# Adafruit_DotStar_Wing.net
KiCad netlist of a schematic drawn in EAGLE
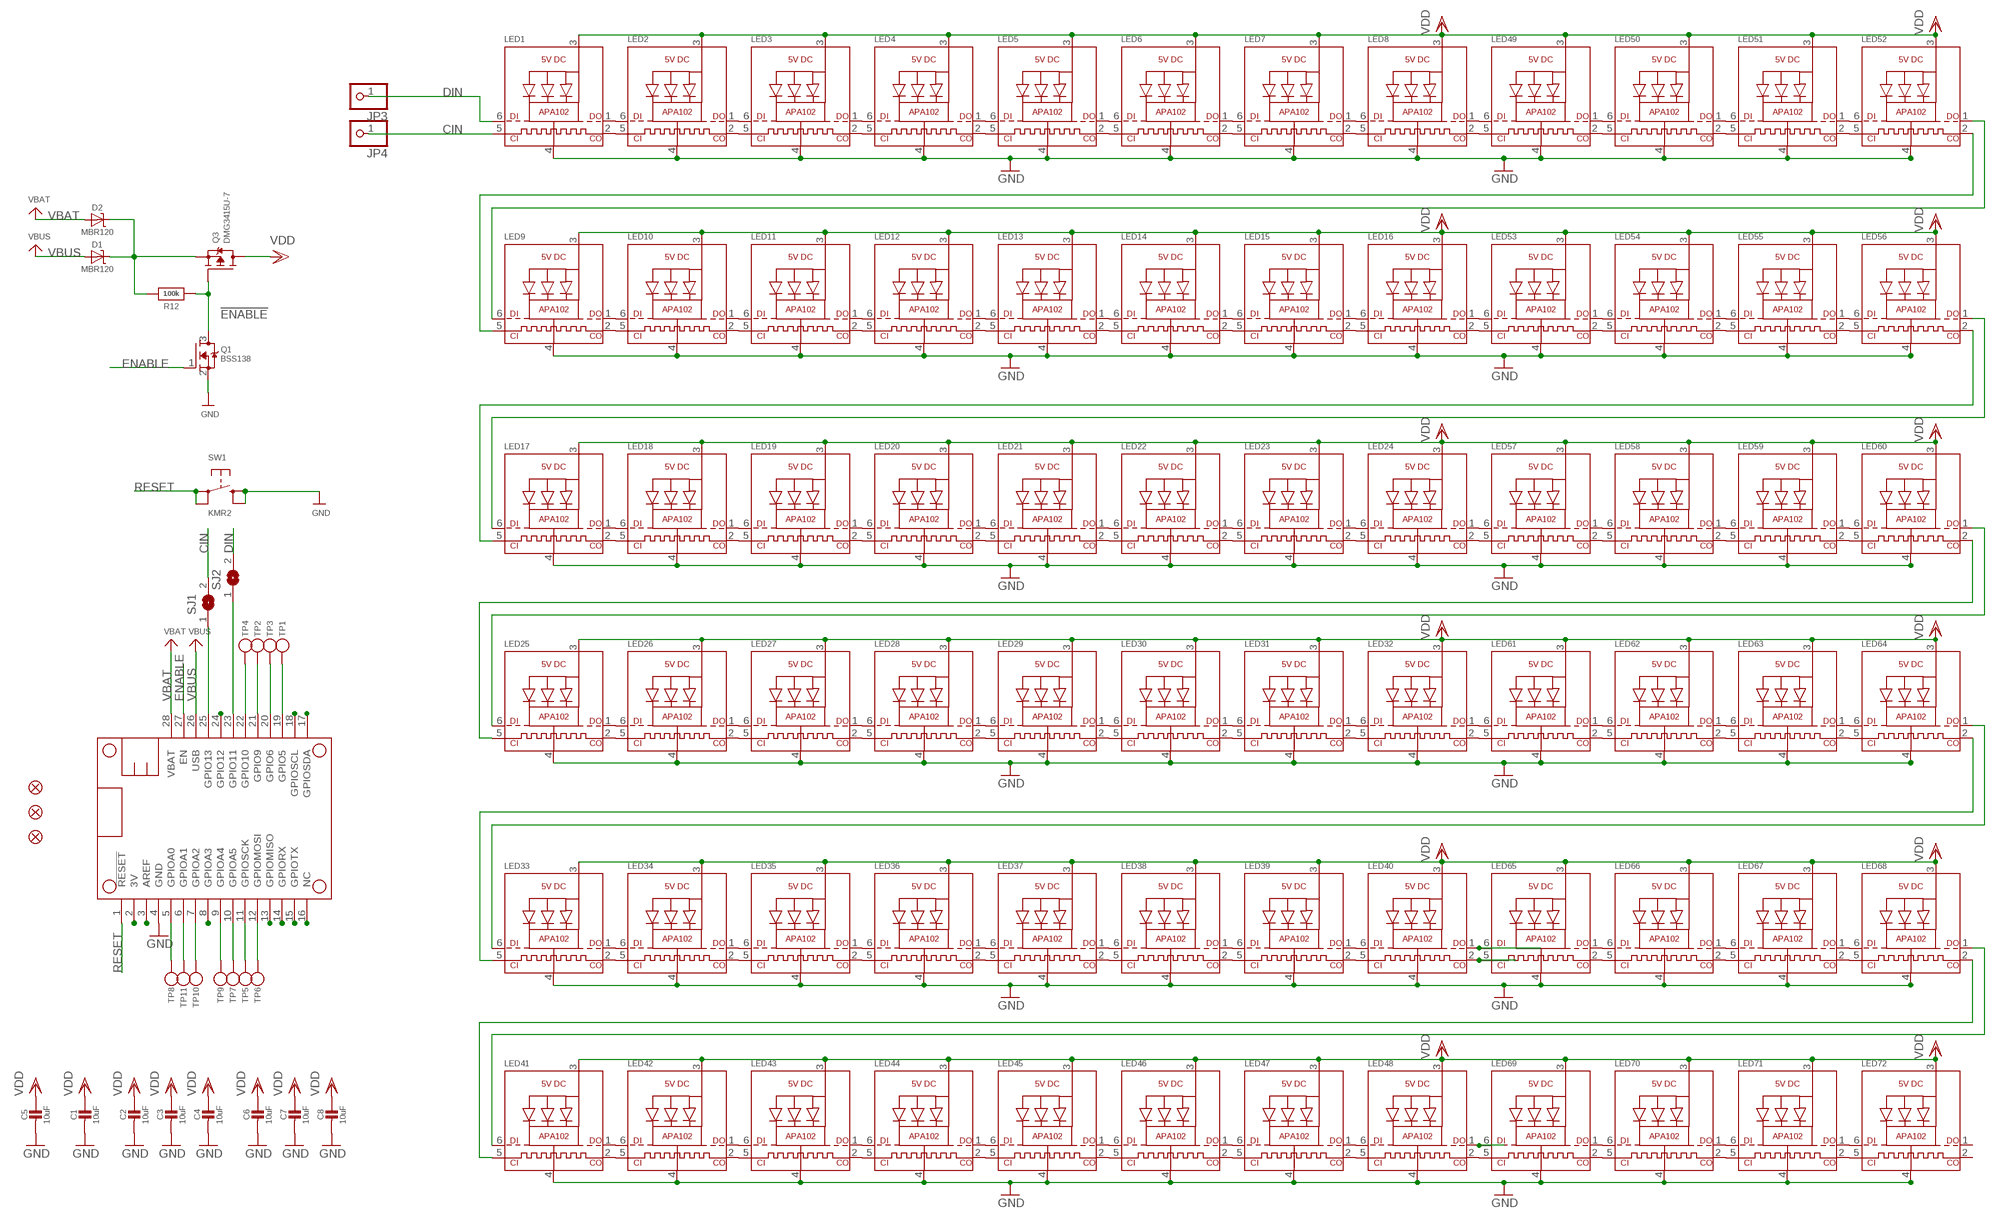
[diagram p0: schematic, sheet 1]

(export (version "E")
  (design (tool "Eeschema 10.0.6"))
  (components
    (comp (ref "C1")
      (value "10uF")
      (footprint "eagle-import:0805-NO")
      (libsource (lib "eagle-import") (part "CAP_CERAMIC0805-NOOUTLINE"))
    )
    (comp (ref "C2")
      (value "10uF")
      (footprint "eagle-import:0805-NO")
      (libsource (lib "eagle-import") (part "CAP_CERAMIC0805-NOOUTLINE"))
    )
    (comp (ref "C3")
      (value "10uF")
      (footprint "eagle-import:0805-NO")
      (libsource (lib "eagle-import") (part "CAP_CERAMIC0805-NOOUTLINE"))
    )
    (comp (ref "C4")
      (value "10uF")
      (footprint "eagle-import:0805-NO")
      (libsource (lib "eagle-import") (part "CAP_CERAMIC0805-NOOUTLINE"))
    )
    (comp (ref "C5")
      (value "10uF")
      (footprint "eagle-import:0805-NO")
      (libsource (lib "eagle-import") (part "CAP_CERAMIC0805-NOOUTLINE"))
    )
    (comp (ref "C6")
      (value "10uF")
      (footprint "eagle-import:0805-NO")
      (libsource (lib "eagle-import") (part "CAP_CERAMIC0805-NOOUTLINE"))
    )
    (comp (ref "C7")
      (value "10uF")
      (footprint "eagle-import:0805-NO")
      (libsource (lib "eagle-import") (part "CAP_CERAMIC0805-NOOUTLINE"))
    )
    (comp (ref "C8")
      (value "10uF")
      (footprint "eagle-import:0805-NO")
      (libsource (lib "eagle-import") (part "CAP_CERAMIC0805-NOOUTLINE"))
    )
    (comp (ref "D1")
      (value "MBR120")
      (footprint "eagle-import:SOD-123")
      (libsource (lib "eagle-import") (part "DIODE-SCHOTTKYSOD-123"))
    )
    (comp (ref "D2")
      (value "MBR120")
      (footprint "eagle-import:SOD-123")
      (libsource (lib "eagle-import") (part "DIODE-SCHOTTKYSOD-123"))
    )
    (comp (ref "FID1")
      (value "FIDUCIAL_1MM")
      (footprint "eagle-import:FIDUCIAL_1MM")
      (libsource (lib "eagle-import") (part "FIDUCIAL_1MM"))
    )
    (comp (ref "FID2")
      (value "FIDUCIAL_1MM")
      (footprint "eagle-import:FIDUCIAL_1MM")
      (libsource (lib "eagle-import") (part "FIDUCIAL_1MM"))
    )
    (comp (ref "FID3")
      (value "FIDUCIAL_1MM")
      (footprint "eagle-import:FIDUCIAL_1MM")
      (libsource (lib "eagle-import") (part "FIDUCIAL_1MM"))
    )
    (comp (ref "JP3")
      (value "HEADER-1X1ROUND")
      (footprint "eagle-import:1X01_ROUND")
      (libsource (lib "eagle-import") (part "HEADER-1X1ROUND"))
    )
    (comp (ref "JP4")
      (value "HEADER-1X1ROUND")
      (footprint "eagle-import:1X01_ROUND")
      (libsource (lib "eagle-import") (part "HEADER-1X1ROUND"))
    )
    (comp (ref "LED1")
      (value "APA1022020")
      (footprint "eagle-import:APA102_2020")
      (libsource (lib "eagle-import") (part "APA1022020"))
    )
    (comp (ref "LED2")
      (value "APA1022020")
      (footprint "eagle-import:APA102_2020")
      (libsource (lib "eagle-import") (part "APA1022020"))
    )
    (comp (ref "LED3")
      (value "APA1022020")
      (footprint "eagle-import:APA102_2020")
      (libsource (lib "eagle-import") (part "APA1022020"))
    )
    (comp (ref "LED4")
      (value "APA1022020")
      (footprint "eagle-import:APA102_2020")
      (libsource (lib "eagle-import") (part "APA1022020"))
    )
    (comp (ref "LED5")
      (value "APA1022020")
      (footprint "eagle-import:APA102_2020")
      (libsource (lib "eagle-import") (part "APA1022020"))
    )
    (comp (ref "LED6")
      (value "APA1022020")
      (footprint "eagle-import:APA102_2020")
      (libsource (lib "eagle-import") (part "APA1022020"))
    )
    (comp (ref "LED7")
      (value "APA1022020")
      (footprint "eagle-import:APA102_2020")
      (libsource (lib "eagle-import") (part "APA1022020"))
    )
    (comp (ref "LED8")
      (value "APA1022020")
      (footprint "eagle-import:APA102_2020")
      (libsource (lib "eagle-import") (part "APA1022020"))
    )
    (comp (ref "LED9")
      (value "APA1022020")
      (footprint "eagle-import:APA102_2020")
      (libsource (lib "eagle-import") (part "APA1022020"))
    )
    (comp (ref "LED10")
      (value "APA1022020")
      (footprint "eagle-import:APA102_2020")
      (libsource (lib "eagle-import") (part "APA1022020"))
    )
    (comp (ref "LED11")
      (value "APA1022020")
      (footprint "eagle-import:APA102_2020")
      (libsource (lib "eagle-import") (part "APA1022020"))
    )
    (comp (ref "LED12")
      (value "APA1022020")
      (footprint "eagle-import:APA102_2020")
      (libsource (lib "eagle-import") (part "APA1022020"))
    )
    (comp (ref "LED13")
      (value "APA1022020")
      (footprint "eagle-import:APA102_2020")
      (libsource (lib "eagle-import") (part "APA1022020"))
    )
    (comp (ref "LED14")
      (value "APA1022020")
      (footprint "eagle-import:APA102_2020")
      (libsource (lib "eagle-import") (part "APA1022020"))
    )
    (comp (ref "LED15")
      (value "APA1022020")
      (footprint "eagle-import:APA102_2020")
      (libsource (lib "eagle-import") (part "APA1022020"))
    )
    (comp (ref "LED16")
      (value "APA1022020")
      (footprint "eagle-import:APA102_2020")
      (libsource (lib "eagle-import") (part "APA1022020"))
    )
    (comp (ref "LED17")
      (value "APA1022020")
      (footprint "eagle-import:APA102_2020")
      (libsource (lib "eagle-import") (part "APA1022020"))
    )
    (comp (ref "LED18")
      (value "APA1022020")
      (footprint "eagle-import:APA102_2020")
      (libsource (lib "eagle-import") (part "APA1022020"))
    )
    (comp (ref "LED19")
      (value "APA1022020")
      (footprint "eagle-import:APA102_2020")
      (libsource (lib "eagle-import") (part "APA1022020"))
    )
    (comp (ref "LED20")
      (value "APA1022020")
      (footprint "eagle-import:APA102_2020")
      (libsource (lib "eagle-import") (part "APA1022020"))
    )
    (comp (ref "LED21")
      (value "APA1022020")
      (footprint "eagle-import:APA102_2020")
      (libsource (lib "eagle-import") (part "APA1022020"))
    )
    (comp (ref "LED22")
      (value "APA1022020")
      (footprint "eagle-import:APA102_2020")
      (libsource (lib "eagle-import") (part "APA1022020"))
    )
    (comp (ref "LED23")
      (value "APA1022020")
      (footprint "eagle-import:APA102_2020")
      (libsource (lib "eagle-import") (part "APA1022020"))
    )
    (comp (ref "LED24")
      (value "APA1022020")
      (footprint "eagle-import:APA102_2020")
      (libsource (lib "eagle-import") (part "APA1022020"))
    )
    (comp (ref "LED25")
      (value "APA1022020")
      (footprint "eagle-import:APA102_2020")
      (libsource (lib "eagle-import") (part "APA1022020"))
    )
    (comp (ref "LED26")
      (value "APA1022020")
      (footprint "eagle-import:APA102_2020")
      (libsource (lib "eagle-import") (part "APA1022020"))
    )
    (comp (ref "LED27")
      (value "APA1022020")
      (footprint "eagle-import:APA102_2020")
      (libsource (lib "eagle-import") (part "APA1022020"))
    )
    (comp (ref "LED28")
      (value "APA1022020")
      (footprint "eagle-import:APA102_2020")
      (libsource (lib "eagle-import") (part "APA1022020"))
    )
    (comp (ref "LED29")
      (value "APA1022020")
      (footprint "eagle-import:APA102_2020")
      (libsource (lib "eagle-import") (part "APA1022020"))
    )
    (comp (ref "LED30")
      (value "APA1022020")
      (footprint "eagle-import:APA102_2020")
      (libsource (lib "eagle-import") (part "APA1022020"))
    )
    (comp (ref "LED31")
      (value "APA1022020")
      (footprint "eagle-import:APA102_2020")
      (libsource (lib "eagle-import") (part "APA1022020"))
    )
    (comp (ref "LED32")
      (value "APA1022020")
      (footprint "eagle-import:APA102_2020")
      (libsource (lib "eagle-import") (part "APA1022020"))
    )
    (comp (ref "LED33")
      (value "APA1022020")
      (footprint "eagle-import:APA102_2020")
      (libsource (lib "eagle-import") (part "APA1022020"))
    )
    (comp (ref "LED34")
      (value "APA1022020")
      (footprint "eagle-import:APA102_2020")
      (libsource (lib "eagle-import") (part "APA1022020"))
    )
    (comp (ref "LED35")
      (value "APA1022020")
      (footprint "eagle-import:APA102_2020")
      (libsource (lib "eagle-import") (part "APA1022020"))
    )
    (comp (ref "LED36")
      (value "APA1022020")
      (footprint "eagle-import:APA102_2020")
      (libsource (lib "eagle-import") (part "APA1022020"))
    )
    (comp (ref "LED37")
      (value "APA1022020")
      (footprint "eagle-import:APA102_2020")
      (libsource (lib "eagle-import") (part "APA1022020"))
    )
    (comp (ref "LED38")
      (value "APA1022020")
      (footprint "eagle-import:APA102_2020")
      (libsource (lib "eagle-import") (part "APA1022020"))
    )
    (comp (ref "LED39")
      (value "APA1022020")
      (footprint "eagle-import:APA102_2020")
      (libsource (lib "eagle-import") (part "APA1022020"))
    )
    (comp (ref "LED40")
      (value "APA1022020")
      (footprint "eagle-import:APA102_2020")
      (libsource (lib "eagle-import") (part "APA1022020"))
    )
    (comp (ref "LED41")
      (value "APA1022020")
      (footprint "eagle-import:APA102_2020")
      (libsource (lib "eagle-import") (part "APA1022020"))
    )
    (comp (ref "LED42")
      (value "APA1022020")
      (footprint "eagle-import:APA102_2020")
      (libsource (lib "eagle-import") (part "APA1022020"))
    )
    (comp (ref "LED43")
      (value "APA1022020")
      (footprint "eagle-import:APA102_2020")
      (libsource (lib "eagle-import") (part "APA1022020"))
    )
    (comp (ref "LED44")
      (value "APA1022020")
      (footprint "eagle-import:APA102_2020")
      (libsource (lib "eagle-import") (part "APA1022020"))
    )
    (comp (ref "LED45")
      (value "APA1022020")
      (footprint "eagle-import:APA102_2020")
      (libsource (lib "eagle-import") (part "APA1022020"))
    )
    (comp (ref "LED46")
      (value "APA1022020")
      (footprint "eagle-import:APA102_2020")
      (libsource (lib "eagle-import") (part "APA1022020"))
    )
    (comp (ref "LED47")
      (value "APA1022020")
      (footprint "eagle-import:APA102_2020")
      (libsource (lib "eagle-import") (part "APA1022020"))
    )
    (comp (ref "LED48")
      (value "APA1022020")
      (footprint "eagle-import:APA102_2020")
      (libsource (lib "eagle-import") (part "APA1022020"))
    )
    (comp (ref "LED49")
      (value "APA1022020")
      (footprint "eagle-import:APA102_2020")
      (libsource (lib "eagle-import") (part "APA1022020"))
    )
    (comp (ref "LED50")
      (value "APA1022020")
      (footprint "eagle-import:APA102_2020")
      (libsource (lib "eagle-import") (part "APA1022020"))
    )
    (comp (ref "LED51")
      (value "APA1022020")
      (footprint "eagle-import:APA102_2020")
      (libsource (lib "eagle-import") (part "APA1022020"))
    )
    (comp (ref "LED52")
      (value "APA1022020")
      (footprint "eagle-import:APA102_2020")
      (libsource (lib "eagle-import") (part "APA1022020"))
    )
    (comp (ref "LED53")
      (value "APA1022020")
      (footprint "eagle-import:APA102_2020")
      (libsource (lib "eagle-import") (part "APA1022020"))
    )
    (comp (ref "LED54")
      (value "APA1022020")
      (footprint "eagle-import:APA102_2020")
      (libsource (lib "eagle-import") (part "APA1022020"))
    )
    (comp (ref "LED55")
      (value "APA1022020")
      (footprint "eagle-import:APA102_2020")
      (libsource (lib "eagle-import") (part "APA1022020"))
    )
    (comp (ref "LED56")
      (value "APA1022020")
      (footprint "eagle-import:APA102_2020")
      (libsource (lib "eagle-import") (part "APA1022020"))
    )
    (comp (ref "LED57")
      (value "APA1022020")
      (footprint "eagle-import:APA102_2020")
      (libsource (lib "eagle-import") (part "APA1022020"))
    )
    (comp (ref "LED58")
      (value "APA1022020")
      (footprint "eagle-import:APA102_2020")
      (libsource (lib "eagle-import") (part "APA1022020"))
    )
    (comp (ref "LED59")
      (value "APA1022020")
      (footprint "eagle-import:APA102_2020")
      (libsource (lib "eagle-import") (part "APA1022020"))
    )
    (comp (ref "LED60")
      (value "APA1022020")
      (footprint "eagle-import:APA102_2020")
      (libsource (lib "eagle-import") (part "APA1022020"))
    )
    (comp (ref "LED61")
      (value "APA1022020")
      (footprint "eagle-import:APA102_2020")
      (libsource (lib "eagle-import") (part "APA1022020"))
    )
    (comp (ref "LED62")
      (value "APA1022020")
      (footprint "eagle-import:APA102_2020")
      (libsource (lib "eagle-import") (part "APA1022020"))
    )
    (comp (ref "LED63")
      (value "APA1022020")
      (footprint "eagle-import:APA102_2020")
      (libsource (lib "eagle-import") (part "APA1022020"))
    )
    (comp (ref "LED64")
      (value "APA1022020")
      (footprint "eagle-import:APA102_2020")
      (libsource (lib "eagle-import") (part "APA1022020"))
    )
    (comp (ref "LED65")
      (value "APA1022020")
      (footprint "eagle-import:APA102_2020")
      (libsource (lib "eagle-import") (part "APA1022020"))
    )
    (comp (ref "LED66")
      (value "APA1022020")
      (footprint "eagle-import:APA102_2020")
      (libsource (lib "eagle-import") (part "APA1022020"))
    )
    (comp (ref "LED67")
      (value "APA1022020")
      (footprint "eagle-import:APA102_2020")
      (libsource (lib "eagle-import") (part "APA1022020"))
    )
    (comp (ref "LED68")
      (value "APA1022020")
      (footprint "eagle-import:APA102_2020")
      (libsource (lib "eagle-import") (part "APA1022020"))
    )
    (comp (ref "LED69")
      (value "APA1022020")
      (footprint "eagle-import:APA102_2020")
      (libsource (lib "eagle-import") (part "APA1022020"))
    )
    (comp (ref "LED70")
      (value "APA1022020")
      (footprint "eagle-import:APA102_2020")
      (libsource (lib "eagle-import") (part "APA1022020"))
    )
    (comp (ref "LED71")
      (value "APA1022020")
      (footprint "eagle-import:APA102_2020")
      (libsource (lib "eagle-import") (part "APA1022020"))
    )
    (comp (ref "LED72")
      (value "APA1022020")
      (footprint "eagle-import:APA102_2020")
      (libsource (lib "eagle-import") (part "APA1022020"))
    )
    (comp (ref "MS1")
      (value "FEATHERWING")
      (footprint "eagle-import:FEATHERWING")
      (libsource (lib "eagle-import") (part "FEATHERWING"))
    )
    (comp (ref "Q1")
      (value "BSS138")
      (footprint "eagle-import:SOT23-WIDE")
      (libsource (lib "eagle-import") (part "MOSFET-NWIDE"))
    )
    (comp (ref "Q3")
      (value "DMG3415U-7")
      (footprint "eagle-import:SOT23-WIDE")
      (libsource (lib "eagle-import") (part "MOSFET-PWIDE"))
    )
    (comp (ref "R12")
      (value "100k")
      (footprint "eagle-import:0603-NO")
      (libsource (lib "eagle-import") (part "RESISTOR_0603_NOOUT"))
    )
    (comp (ref "SJ1")
      (value "SOLDERJUMPERCLOSED")
      (footprint "eagle-import:SOLDERJUMPER_CLOSEDWIRE")
      (libsource (lib "eagle-import") (part "SOLDERJUMPERCLOSED"))
    )
    (comp (ref "SJ2")
      (value "SOLDERJUMPERCLOSED")
      (footprint "eagle-import:SOLDERJUMPER_CLOSEDWIRE")
      (libsource (lib "eagle-import") (part "SOLDERJUMPERCLOSED"))
    )
    (comp (ref "SW1")
      (value "KMR2")
      (footprint "eagle-import:BTN_KMR2_4.6X2.8")
      (libsource (lib "eagle-import") (part "SWITCH_TACT_SMT4.6X2.8"))
    )
    (comp (ref "TP1")
      (value "TESTPOINT1.5X2.0MM_NOCREAM")
      (footprint "eagle-import:PAD-1.5X2.0")
      (libsource (lib "eagle-import") (part "TESTPOINT1.5X2.0MM_NOCREAM"))
    )
    (comp (ref "TP2")
      (value "TESTPOINT1.5X2.0MM_NOCREAM")
      (footprint "eagle-import:PAD-1.5X2.0")
      (libsource (lib "eagle-import") (part "TESTPOINT1.5X2.0MM_NOCREAM"))
    )
    (comp (ref "TP3")
      (value "TESTPOINT1.5X2.0MM_NOCREAM")
      (footprint "eagle-import:PAD-1.5X2.0")
      (libsource (lib "eagle-import") (part "TESTPOINT1.5X2.0MM_NOCREAM"))
    )
    (comp (ref "TP4")
      (value "TESTPOINT1.5X2.0MM_NOCREAM")
      (footprint "eagle-import:PAD-1.5X2.0")
      (libsource (lib "eagle-import") (part "TESTPOINT1.5X2.0MM_NOCREAM"))
    )
    (comp (ref "TP5")
      (value "TESTPOINT1.5X2.0MM_NOCREAM")
      (footprint "eagle-import:PAD-1.5X2.0")
      (libsource (lib "eagle-import") (part "TESTPOINT1.5X2.0MM_NOCREAM"))
    )
    (comp (ref "TP6")
      (value "TESTPOINT1.5X2.0MM_NOCREAM")
      (footprint "eagle-import:PAD-1.5X2.0")
      (libsource (lib "eagle-import") (part "TESTPOINT1.5X2.0MM_NOCREAM"))
    )
    (comp (ref "TP7")
      (value "TESTPOINT1.5X2.0MM_NOCREAM")
      (footprint "eagle-import:PAD-1.5X2.0")
      (libsource (lib "eagle-import") (part "TESTPOINT1.5X2.0MM_NOCREAM"))
    )
    (comp (ref "TP8")
      (value "TESTPOINT1.5X2.0MM_NOCREAM")
      (footprint "eagle-import:PAD-1.5X2.0")
      (libsource (lib "eagle-import") (part "TESTPOINT1.5X2.0MM_NOCREAM"))
    )
    (comp (ref "TP9")
      (value "TESTPOINT1.5X2.0MM_NOCREAM")
      (footprint "eagle-import:PAD-1.5X2.0")
      (libsource (lib "eagle-import") (part "TESTPOINT1.5X2.0MM_NOCREAM"))
    )
    (comp (ref "TP10")
      (value "TESTPOINT1.5X2.0MM_NOCREAM")
      (footprint "eagle-import:PAD-1.5X2.0")
      (libsource (lib "eagle-import") (part "TESTPOINT1.5X2.0MM_NOCREAM"))
    )
    (comp (ref "TP11")
      (value "TESTPOINT1.5X2.0MM_NOCREAM")
      (footprint "eagle-import:PAD-1.5X2.0")
      (libsource (lib "eagle-import") (part "TESTPOINT1.5X2.0MM_NOCREAM"))
    )
  )
  (nets
    (net (code "1") (name "/3V") (class "Default")
      (node (ref "MS1") (pin "2") (pinfunction "3V_2") (pintype "power_in"))
    )
    (net (code "2") (name "/CIN") (class "Default")
      (node (ref "JP4") (pin "1") (pinfunction "1_1") (pintype "passive"))
      (node (ref "LED1") (pin "5") (pinfunction "CKI_5") (pintype "input"))
      (node (ref "SJ1") (pin "2") (pinfunction "2_2") (pintype "passive"))
    )
    (net (code "3") (name "/DIN") (class "Default")
      (node (ref "JP3") (pin "1") (pinfunction "1_1") (pintype "passive"))
      (node (ref "LED1") (pin "6") (pinfunction "DI_6") (pintype "input"))
      (node (ref "SJ2") (pin "2") (pinfunction "2_2") (pintype "passive"))
    )
    (net (code "4") (name "/ENABLE") (class "Default")
      (node (ref "MS1") (pin "27") (pinfunction "EN_27") (pintype "passive"))
      (node (ref "Q1") (pin "1") (pinfunction "G_1") (pintype "bidirectional"))
    )
    (net (code "5") (name "/RESET") (class "Default")
      (node (ref "MS1") (pin "1") (pinfunction "~{RESET}_1") (pintype "input"))
      (node (ref "SW1") (pin "A") (pinfunction "P_A") (pintype "passive"))
      (node (ref "SW1") (pin "A'") (pinfunction "P1_A'") (pintype "passive"))
    )
    (net (code "6") (name "/~{ENABLE}") (class "Default")
      (node (ref "Q1") (pin "3") (pinfunction "D_3") (pintype "bidirectional"))
      (node (ref "Q3") (pin "1") (pinfunction "G_1") (pintype "passive"))
      (node (ref "R12") (pin "1") (pinfunction "1_1") (pintype "passive"))
    )
    (net (code "7") (name "GND") (class "Default")
      (node (ref "C1") (pin "2") (pinfunction "2_2") (pintype "passive"))
      (node (ref "C2") (pin "2") (pinfunction "2_2") (pintype "passive"))
      (node (ref "C3") (pin "2") (pinfunction "2_2") (pintype "passive"))
      (node (ref "C4") (pin "2") (pinfunction "2_2") (pintype "passive"))
      (node (ref "C5") (pin "2") (pinfunction "2_2") (pintype "passive"))
      (node (ref "C6") (pin "2") (pinfunction "2_2") (pintype "passive"))
      (node (ref "C7") (pin "2") (pinfunction "2_2") (pintype "passive"))
      (node (ref "C8") (pin "2") (pinfunction "2_2") (pintype "passive"))
      (node (ref "LED1") (pin "4") (pinfunction "GND_4") (pintype "power_in"))
      (node (ref "LED10") (pin "4") (pinfunction "GND_4") (pintype "power_in"))
      (node (ref "LED11") (pin "4") (pinfunction "GND_4") (pintype "power_in"))
      (node (ref "LED12") (pin "4") (pinfunction "GND_4") (pintype "power_in"))
      (node (ref "LED13") (pin "4") (pinfunction "GND_4") (pintype "power_in"))
      (node (ref "LED14") (pin "4") (pinfunction "GND_4") (pintype "power_in"))
      (node (ref "LED15") (pin "4") (pinfunction "GND_4") (pintype "power_in"))
      (node (ref "LED16") (pin "4") (pinfunction "GND_4") (pintype "power_in"))
      (node (ref "LED17") (pin "4") (pinfunction "GND_4") (pintype "power_in"))
      (node (ref "LED18") (pin "4") (pinfunction "GND_4") (pintype "power_in"))
      (node (ref "LED19") (pin "4") (pinfunction "GND_4") (pintype "power_in"))
      (node (ref "LED2") (pin "4") (pinfunction "GND_4") (pintype "power_in"))
      (node (ref "LED20") (pin "4") (pinfunction "GND_4") (pintype "power_in"))
      (node (ref "LED21") (pin "4") (pinfunction "GND_4") (pintype "power_in"))
      (node (ref "LED22") (pin "4") (pinfunction "GND_4") (pintype "power_in"))
      (node (ref "LED23") (pin "4") (pinfunction "GND_4") (pintype "power_in"))
      (node (ref "LED24") (pin "4") (pinfunction "GND_4") (pintype "power_in"))
      (node (ref "LED25") (pin "4") (pinfunction "GND_4") (pintype "power_in"))
      (node (ref "LED26") (pin "4") (pinfunction "GND_4") (pintype "power_in"))
      (node (ref "LED27") (pin "4") (pinfunction "GND_4") (pintype "power_in"))
      (node (ref "LED28") (pin "4") (pinfunction "GND_4") (pintype "power_in"))
      (node (ref "LED29") (pin "4") (pinfunction "GND_4") (pintype "power_in"))
      (node (ref "LED3") (pin "4") (pinfunction "GND_4") (pintype "power_in"))
      (node (ref "LED30") (pin "4") (pinfunction "GND_4") (pintype "power_in"))
      (node (ref "LED31") (pin "4") (pinfunction "GND_4") (pintype "power_in"))
      (node (ref "LED32") (pin "4") (pinfunction "GND_4") (pintype "power_in"))
      (node (ref "LED33") (pin "4") (pinfunction "GND_4") (pintype "power_in"))
      (node (ref "LED34") (pin "4") (pinfunction "GND_4") (pintype "power_in"))
      (node (ref "LED35") (pin "4") (pinfunction "GND_4") (pintype "power_in"))
      (node (ref "LED36") (pin "4") (pinfunction "GND_4") (pintype "power_in"))
      (node (ref "LED37") (pin "4") (pinfunction "GND_4") (pintype "power_in"))
      (node (ref "LED38") (pin "4") (pinfunction "GND_4") (pintype "power_in"))
      (node (ref "LED39") (pin "4") (pinfunction "GND_4") (pintype "power_in"))
      (node (ref "LED4") (pin "4") (pinfunction "GND_4") (pintype "power_in"))
      (node (ref "LED40") (pin "4") (pinfunction "GND_4") (pintype "power_in"))
      (node (ref "LED41") (pin "4") (pinfunction "GND_4") (pintype "power_in"))
      (node (ref "LED42") (pin "4") (pinfunction "GND_4") (pintype "power_in"))
      (node (ref "LED43") (pin "4") (pinfunction "GND_4") (pintype "power_in"))
      (node (ref "LED44") (pin "4") (pinfunction "GND_4") (pintype "power_in"))
      (node (ref "LED45") (pin "4") (pinfunction "GND_4") (pintype "power_in"))
      (node (ref "LED46") (pin "4") (pinfunction "GND_4") (pintype "power_in"))
      (node (ref "LED47") (pin "4") (pinfunction "GND_4") (pintype "power_in"))
      (node (ref "LED48") (pin "4") (pinfunction "GND_4") (pintype "power_in"))
      (node (ref "LED49") (pin "4") (pinfunction "GND_4") (pintype "power_in"))
      (node (ref "LED5") (pin "4") (pinfunction "GND_4") (pintype "power_in"))
      (node (ref "LED50") (pin "4") (pinfunction "GND_4") (pintype "power_in"))
      (node (ref "LED51") (pin "4") (pinfunction "GND_4") (pintype "power_in"))
      (node (ref "LED52") (pin "4") (pinfunction "GND_4") (pintype "power_in"))
      (node (ref "LED53") (pin "4") (pinfunction "GND_4") (pintype "power_in"))
      (node (ref "LED54") (pin "4") (pinfunction "GND_4") (pintype "power_in"))
      (node (ref "LED55") (pin "4") (pinfunction "GND_4") (pintype "power_in"))
      (node (ref "LED56") (pin "4") (pinfunction "GND_4") (pintype "power_in"))
      (node (ref "LED57") (pin "4") (pinfunction "GND_4") (pintype "power_in"))
      (node (ref "LED58") (pin "4") (pinfunction "GND_4") (pintype "power_in"))
      (node (ref "LED59") (pin "4") (pinfunction "GND_4") (pintype "power_in"))
      (node (ref "LED6") (pin "4") (pinfunction "GND_4") (pintype "power_in"))
      (node (ref "LED60") (pin "4") (pinfunction "GND_4") (pintype "power_in"))
      (node (ref "LED61") (pin "4") (pinfunction "GND_4") (pintype "power_in"))
      (node (ref "LED62") (pin "4") (pinfunction "GND_4") (pintype "power_in"))
      (node (ref "LED63") (pin "4") (pinfunction "GND_4") (pintype "power_in"))
      (node (ref "LED64") (pin "4") (pinfunction "GND_4") (pintype "power_in"))
      (node (ref "LED65") (pin "4") (pinfunction "GND_4") (pintype "power_in"))
      (node (ref "LED66") (pin "4") (pinfunction "GND_4") (pintype "power_in"))
      (node (ref "LED67") (pin "4") (pinfunction "GND_4") (pintype "power_in"))
      (node (ref "LED68") (pin "4") (pinfunction "GND_4") (pintype "power_in"))
      (node (ref "LED69") (pin "4") (pinfunction "GND_4") (pintype "power_in"))
      (node (ref "LED7") (pin "4") (pinfunction "GND_4") (pintype "power_in"))
      (node (ref "LED70") (pin "4") (pinfunction "GND_4") (pintype "power_in"))
      (node (ref "LED71") (pin "4") (pinfunction "GND_4") (pintype "power_in"))
      (node (ref "LED72") (pin "4") (pinfunction "GND_4") (pintype "power_in"))
      (node (ref "LED8") (pin "4") (pinfunction "GND_4") (pintype "power_in"))
      (node (ref "LED9") (pin "4") (pinfunction "GND_4") (pintype "power_in"))
      (node (ref "MS1") (pin "4") (pinfunction "GND_4") (pintype "power_in"))
      (node (ref "Q1") (pin "2") (pinfunction "S_2") (pintype "bidirectional"))
      (node (ref "SW1") (pin "B") (pinfunction "S_B") (pintype "passive"))
      (node (ref "SW1") (pin "B'") (pinfunction "S1_B'") (pintype "passive"))
    )
    (net (code "8") (name "Net-(LED1-CKO)") (class "Default")
      (node (ref "LED1") (pin "2") (pinfunction "CKO_2") (pintype "output"))
      (node (ref "LED2") (pin "5") (pinfunction "CKI_5") (pintype "input"))
    )
    (net (code "9") (name "Net-(LED1-DO)") (class "Default")
      (node (ref "LED1") (pin "1") (pinfunction "DO_1") (pintype "output"))
      (node (ref "LED2") (pin "6") (pinfunction "DI_6") (pintype "input"))
    )
    (net (code "10") (name "Net-(LED2-CKO)") (class "Default")
      (node (ref "LED2") (pin "2") (pinfunction "CKO_2") (pintype "output"))
      (node (ref "LED3") (pin "5") (pinfunction "CKI_5") (pintype "input"))
    )
    (net (code "11") (name "Net-(LED2-DO)") (class "Default")
      (node (ref "LED2") (pin "1") (pinfunction "DO_1") (pintype "output"))
      (node (ref "LED3") (pin "6") (pinfunction "DI_6") (pintype "input"))
    )
    (net (code "12") (name "Net-(LED3-CKO)") (class "Default")
      (node (ref "LED3") (pin "2") (pinfunction "CKO_2") (pintype "output"))
      (node (ref "LED4") (pin "5") (pinfunction "CKI_5") (pintype "input"))
    )
    (net (code "13") (name "Net-(LED3-DO)") (class "Default")
      (node (ref "LED3") (pin "1") (pinfunction "DO_1") (pintype "output"))
      (node (ref "LED4") (pin "6") (pinfunction "DI_6") (pintype "input"))
    )
    (net (code "14") (name "Net-(LED4-CKO)") (class "Default")
      (node (ref "LED4") (pin "2") (pinfunction "CKO_2") (pintype "output"))
      (node (ref "LED5") (pin "5") (pinfunction "CKI_5") (pintype "input"))
    )
    (net (code "15") (name "Net-(LED4-DO)") (class "Default")
      (node (ref "LED4") (pin "1") (pinfunction "DO_1") (pintype "output"))
      (node (ref "LED5") (pin "6") (pinfunction "DI_6") (pintype "input"))
    )
    (net (code "16") (name "Net-(LED5-CKO)") (class "Default")
      (node (ref "LED5") (pin "2") (pinfunction "CKO_2") (pintype "output"))
      (node (ref "LED6") (pin "5") (pinfunction "CKI_5") (pintype "input"))
    )
    (net (code "17") (name "Net-(LED5-DO)") (class "Default")
      (node (ref "LED5") (pin "1") (pinfunction "DO_1") (pintype "output"))
      (node (ref "LED6") (pin "6") (pinfunction "DI_6") (pintype "input"))
    )
    (net (code "18") (name "Net-(LED6-CKO)") (class "Default")
      (node (ref "LED6") (pin "2") (pinfunction "CKO_2") (pintype "output"))
      (node (ref "LED7") (pin "5") (pinfunction "CKI_5") (pintype "input"))
    )
    (net (code "19") (name "Net-(LED6-DO)") (class "Default")
      (node (ref "LED6") (pin "1") (pinfunction "DO_1") (pintype "output"))
      (node (ref "LED7") (pin "6") (pinfunction "DI_6") (pintype "input"))
    )
    (net (code "20") (name "Net-(LED7-CKO)") (class "Default")
      (node (ref "LED7") (pin "2") (pinfunction "CKO_2") (pintype "output"))
      (node (ref "LED8") (pin "5") (pinfunction "CKI_5") (pintype "input"))
    )
    (net (code "21") (name "Net-(LED7-DO)") (class "Default")
      (node (ref "LED7") (pin "1") (pinfunction "DO_1") (pintype "output"))
      (node (ref "LED8") (pin "6") (pinfunction "DI_6") (pintype "input"))
    )
    (net (code "22") (name "Net-(LED10-CKI)") (class "Default")
      (node (ref "LED10") (pin "5") (pinfunction "CKI_5") (pintype "input"))
      (node (ref "LED9") (pin "2") (pinfunction "CKO_2") (pintype "output"))
    )
    (net (code "23") (name "Net-(LED10-CKO)") (class "Default")
      (node (ref "LED10") (pin "2") (pinfunction "CKO_2") (pintype "output"))
      (node (ref "LED11") (pin "5") (pinfunction "CKI_5") (pintype "input"))
    )
    (net (code "24") (name "Net-(LED10-DI)") (class "Default")
      (node (ref "LED10") (pin "6") (pinfunction "DI_6") (pintype "input"))
      (node (ref "LED9") (pin "1") (pinfunction "DO_1") (pintype "output"))
    )
    (net (code "25") (name "Net-(LED10-DO)") (class "Default")
      (node (ref "LED10") (pin "1") (pinfunction "DO_1") (pintype "output"))
      (node (ref "LED11") (pin "6") (pinfunction "DI_6") (pintype "input"))
    )
    (net (code "26") (name "Net-(LED11-CKO)") (class "Default")
      (node (ref "LED11") (pin "2") (pinfunction "CKO_2") (pintype "output"))
      (node (ref "LED12") (pin "5") (pinfunction "CKI_5") (pintype "input"))
    )
    (net (code "27") (name "Net-(LED11-DO)") (class "Default")
      (node (ref "LED11") (pin "1") (pinfunction "DO_1") (pintype "output"))
      (node (ref "LED12") (pin "6") (pinfunction "DI_6") (pintype "input"))
    )
    (net (code "28") (name "Net-(LED12-CKO)") (class "Default")
      (node (ref "LED12") (pin "2") (pinfunction "CKO_2") (pintype "output"))
      (node (ref "LED13") (pin "5") (pinfunction "CKI_5") (pintype "input"))
    )
    (net (code "29") (name "Net-(LED12-DO)") (class "Default")
      (node (ref "LED12") (pin "1") (pinfunction "DO_1") (pintype "output"))
      (node (ref "LED13") (pin "6") (pinfunction "DI_6") (pintype "input"))
    )
    (net (code "30") (name "Net-(LED13-CKO)") (class "Default")
      (node (ref "LED13") (pin "2") (pinfunction "CKO_2") (pintype "output"))
      (node (ref "LED14") (pin "5") (pinfunction "CKI_5") (pintype "input"))
    )
    (net (code "31") (name "Net-(LED13-DO)") (class "Default")
      (node (ref "LED13") (pin "1") (pinfunction "DO_1") (pintype "output"))
      (node (ref "LED14") (pin "6") (pinfunction "DI_6") (pintype "input"))
    )
    (net (code "32") (name "Net-(LED14-CKO)") (class "Default")
      (node (ref "LED14") (pin "2") (pinfunction "CKO_2") (pintype "output"))
      (node (ref "LED15") (pin "5") (pinfunction "CKI_5") (pintype "input"))
    )
    (net (code "33") (name "Net-(LED14-DO)") (class "Default")
      (node (ref "LED14") (pin "1") (pinfunction "DO_1") (pintype "output"))
      (node (ref "LED15") (pin "6") (pinfunction "DI_6") (pintype "input"))
    )
    (net (code "34") (name "Net-(LED15-CKO)") (class "Default")
      (node (ref "LED15") (pin "2") (pinfunction "CKO_2") (pintype "output"))
      (node (ref "LED16") (pin "5") (pinfunction "CKI_5") (pintype "input"))
    )
    (net (code "35") (name "Net-(LED15-DO)") (class "Default")
      (node (ref "LED15") (pin "1") (pinfunction "DO_1") (pintype "output"))
      (node (ref "LED16") (pin "6") (pinfunction "DI_6") (pintype "input"))
    )
    (net (code "36") (name "Net-(LED16-CKO)") (class "Default")
      (node (ref "LED16") (pin "2") (pinfunction "CKO_2") (pintype "output"))
      (node (ref "LED53") (pin "5") (pinfunction "CKI_5") (pintype "input"))
    )
    (net (code "37") (name "Net-(LED16-DO)") (class "Default")
      (node (ref "LED16") (pin "1") (pinfunction "DO_1") (pintype "output"))
      (node (ref "LED53") (pin "6") (pinfunction "DI_6") (pintype "input"))
    )
    (net (code "38") (name "Net-(LED17-CKI)") (class "Default")
      (node (ref "LED17") (pin "5") (pinfunction "CKI_5") (pintype "input"))
      (node (ref "LED56") (pin "2") (pinfunction "CKO_2") (pintype "output"))
    )
    (net (code "39") (name "Net-(LED17-CKO)") (class "Default")
      (node (ref "LED17") (pin "2") (pinfunction "CKO_2") (pintype "output"))
      (node (ref "LED18") (pin "5") (pinfunction "CKI_5") (pintype "input"))
    )
    (net (code "40") (name "Net-(LED17-DI)") (class "Default")
      (node (ref "LED17") (pin "6") (pinfunction "DI_6") (pintype "input"))
      (node (ref "LED56") (pin "1") (pinfunction "DO_1") (pintype "output"))
    )
    (net (code "41") (name "Net-(LED17-DO)") (class "Default")
      (node (ref "LED17") (pin "1") (pinfunction "DO_1") (pintype "output"))
      (node (ref "LED18") (pin "6") (pinfunction "DI_6") (pintype "input"))
    )
    (net (code "42") (name "Net-(LED18-CKO)") (class "Default")
      (node (ref "LED18") (pin "2") (pinfunction "CKO_2") (pintype "output"))
      (node (ref "LED19") (pin "5") (pinfunction "CKI_5") (pintype "input"))
    )
    (net (code "43") (name "Net-(LED18-DO)") (class "Default")
      (node (ref "LED18") (pin "1") (pinfunction "DO_1") (pintype "output"))
      (node (ref "LED19") (pin "6") (pinfunction "DI_6") (pintype "input"))
    )
    (net (code "44") (name "Net-(LED19-CKO)") (class "Default")
      (node (ref "LED19") (pin "2") (pinfunction "CKO_2") (pintype "output"))
      (node (ref "LED20") (pin "5") (pinfunction "CKI_5") (pintype "input"))
    )
    (net (code "45") (name "Net-(LED19-DO)") (class "Default")
      (node (ref "LED19") (pin "1") (pinfunction "DO_1") (pintype "output"))
      (node (ref "LED20") (pin "6") (pinfunction "DI_6") (pintype "input"))
    )
    (net (code "46") (name "Net-(LED20-CKO)") (class "Default")
      (node (ref "LED20") (pin "2") (pinfunction "CKO_2") (pintype "output"))
      (node (ref "LED21") (pin "5") (pinfunction "CKI_5") (pintype "input"))
    )
    (net (code "47") (name "Net-(LED20-DO)") (class "Default")
      (node (ref "LED20") (pin "1") (pinfunction "DO_1") (pintype "output"))
      (node (ref "LED21") (pin "6") (pinfunction "DI_6") (pintype "input"))
    )
    (net (code "48") (name "Net-(LED21-CKO)") (class "Default")
      (node (ref "LED21") (pin "2") (pinfunction "CKO_2") (pintype "output"))
      (node (ref "LED22") (pin "5") (pinfunction "CKI_5") (pintype "input"))
    )
    (net (code "49") (name "Net-(LED21-DO)") (class "Default")
      (node (ref "LED21") (pin "1") (pinfunction "DO_1") (pintype "output"))
      (node (ref "LED22") (pin "6") (pinfunction "DI_6") (pintype "input"))
    )
    (net (code "50") (name "Net-(LED22-CKO)") (class "Default")
      (node (ref "LED22") (pin "2") (pinfunction "CKO_2") (pintype "output"))
      (node (ref "LED23") (pin "5") (pinfunction "CKI_5") (pintype "input"))
    )
    (net (code "51") (name "Net-(LED22-DO)") (class "Default")
      (node (ref "LED22") (pin "1") (pinfunction "DO_1") (pintype "output"))
      (node (ref "LED23") (pin "6") (pinfunction "DI_6") (pintype "input"))
    )
    (net (code "52") (name "Net-(LED23-CKO)") (class "Default")
      (node (ref "LED23") (pin "2") (pinfunction "CKO_2") (pintype "output"))
      (node (ref "LED24") (pin "5") (pinfunction "CKI_5") (pintype "input"))
    )
    (net (code "53") (name "Net-(LED23-DO)") (class "Default")
      (node (ref "LED23") (pin "1") (pinfunction "DO_1") (pintype "output"))
      (node (ref "LED24") (pin "6") (pinfunction "DI_6") (pintype "input"))
    )
    (net (code "54") (name "Net-(LED24-CKO)") (class "Default")
      (node (ref "LED24") (pin "2") (pinfunction "CKO_2") (pintype "output"))
      (node (ref "LED57") (pin "5") (pinfunction "CKI_5") (pintype "input"))
    )
    (net (code "55") (name "Net-(LED24-DO)") (class "Default")
      (node (ref "LED24") (pin "1") (pinfunction "DO_1") (pintype "output"))
      (node (ref "LED57") (pin "6") (pinfunction "DI_6") (pintype "input"))
    )
    (net (code "56") (name "Net-(LED25-CKI)") (class "Default")
      (node (ref "LED25") (pin "5") (pinfunction "CKI_5") (pintype "input"))
      (node (ref "LED60") (pin "2") (pinfunction "CKO_2") (pintype "output"))
    )
    (net (code "57") (name "Net-(LED25-CKO)") (class "Default")
      (node (ref "LED25") (pin "2") (pinfunction "CKO_2") (pintype "output"))
      (node (ref "LED26") (pin "5") (pinfunction "CKI_5") (pintype "input"))
    )
    (net (code "58") (name "Net-(LED25-DI)") (class "Default")
      (node (ref "LED25") (pin "6") (pinfunction "DI_6") (pintype "input"))
      (node (ref "LED60") (pin "1") (pinfunction "DO_1") (pintype "output"))
    )
    (net (code "59") (name "Net-(LED25-DO)") (class "Default")
      (node (ref "LED25") (pin "1") (pinfunction "DO_1") (pintype "output"))
      (node (ref "LED26") (pin "6") (pinfunction "DI_6") (pintype "input"))
    )
    (net (code "60") (name "Net-(LED26-CKO)") (class "Default")
      (node (ref "LED26") (pin "2") (pinfunction "CKO_2") (pintype "output"))
      (node (ref "LED27") (pin "5") (pinfunction "CKI_5") (pintype "input"))
    )
    (net (code "61") (name "Net-(LED26-DO)") (class "Default")
      (node (ref "LED26") (pin "1") (pinfunction "DO_1") (pintype "output"))
      (node (ref "LED27") (pin "6") (pinfunction "DI_6") (pintype "input"))
    )
    (net (code "62") (name "Net-(LED27-CKO)") (class "Default")
      (node (ref "LED27") (pin "2") (pinfunction "CKO_2") (pintype "output"))
      (node (ref "LED28") (pin "5") (pinfunction "CKI_5") (pintype "input"))
    )
    (net (code "63") (name "Net-(LED27-DO)") (class "Default")
      (node (ref "LED27") (pin "1") (pinfunction "DO_1") (pintype "output"))
      (node (ref "LED28") (pin "6") (pinfunction "DI_6") (pintype "input"))
    )
    (net (code "64") (name "Net-(LED28-CKO)") (class "Default")
      (node (ref "LED28") (pin "2") (pinfunction "CKO_2") (pintype "output"))
      (node (ref "LED29") (pin "5") (pinfunction "CKI_5") (pintype "input"))
    )
    (net (code "65") (name "Net-(LED28-DO)") (class "Default")
      (node (ref "LED28") (pin "1") (pinfunction "DO_1") (pintype "output"))
      (node (ref "LED29") (pin "6") (pinfunction "DI_6") (pintype "input"))
    )
    (net (code "66") (name "Net-(LED29-CKO)") (class "Default")
      (node (ref "LED29") (pin "2") (pinfunction "CKO_2") (pintype "output"))
      (node (ref "LED30") (pin "5") (pinfunction "CKI_5") (pintype "input"))
    )
    (net (code "67") (name "Net-(LED29-DO)") (class "Default")
      (node (ref "LED29") (pin "1") (pinfunction "DO_1") (pintype "output"))
      (node (ref "LED30") (pin "6") (pinfunction "DI_6") (pintype "input"))
    )
    (net (code "68") (name "Net-(LED30-CKO)") (class "Default")
      (node (ref "LED30") (pin "2") (pinfunction "CKO_2") (pintype "output"))
      (node (ref "LED31") (pin "5") (pinfunction "CKI_5") (pintype "input"))
    )
    (net (code "69") (name "Net-(LED30-DO)") (class "Default")
      (node (ref "LED30") (pin "1") (pinfunction "DO_1") (pintype "output"))
      (node (ref "LED31") (pin "6") (pinfunction "DI_6") (pintype "input"))
    )
    (net (code "70") (name "Net-(LED31-CKO)") (class "Default")
      (node (ref "LED31") (pin "2") (pinfunction "CKO_2") (pintype "output"))
      (node (ref "LED32") (pin "5") (pinfunction "CKI_5") (pintype "input"))
    )
    (net (code "71") (name "Net-(LED31-DO)") (class "Default")
      (node (ref "LED31") (pin "1") (pinfunction "DO_1") (pintype "output"))
      (node (ref "LED32") (pin "6") (pinfunction "DI_6") (pintype "input"))
    )
    (net (code "72") (name "Net-(LED32-CKO)") (class "Default")
      (node (ref "LED32") (pin "2") (pinfunction "CKO_2") (pintype "output"))
      (node (ref "LED61") (pin "5") (pinfunction "CKI_5") (pintype "input"))
    )
    (net (code "73") (name "Net-(LED32-DO)") (class "Default")
      (node (ref "LED32") (pin "1") (pinfunction "DO_1") (pintype "output"))
      (node (ref "LED61") (pin "6") (pinfunction "DI_6") (pintype "input"))
    )
    (net (code "74") (name "Net-(LED33-CKI)") (class "Default")
      (node (ref "LED33") (pin "5") (pinfunction "CKI_5") (pintype "input"))
      (node (ref "LED64") (pin "2") (pinfunction "CKO_2") (pintype "output"))
    )
    (net (code "75") (name "Net-(LED33-CKO)") (class "Default")
      (node (ref "LED33") (pin "2") (pinfunction "CKO_2") (pintype "output"))
      (node (ref "LED34") (pin "5") (pinfunction "CKI_5") (pintype "input"))
    )
    (net (code "76") (name "Net-(LED33-DI)") (class "Default")
      (node (ref "LED33") (pin "6") (pinfunction "DI_6") (pintype "input"))
      (node (ref "LED64") (pin "1") (pinfunction "DO_1") (pintype "output"))
    )
    (net (code "77") (name "Net-(LED33-DO)") (class "Default")
      (node (ref "LED33") (pin "1") (pinfunction "DO_1") (pintype "output"))
      (node (ref "LED34") (pin "6") (pinfunction "DI_6") (pintype "input"))
    )
    (net (code "78") (name "Net-(LED34-CKO)") (class "Default")
      (node (ref "LED34") (pin "2") (pinfunction "CKO_2") (pintype "output"))
      (node (ref "LED35") (pin "5") (pinfunction "CKI_5") (pintype "input"))
    )
    (net (code "79") (name "Net-(LED34-DO)") (class "Default")
      (node (ref "LED34") (pin "1") (pinfunction "DO_1") (pintype "output"))
      (node (ref "LED35") (pin "6") (pinfunction "DI_6") (pintype "input"))
    )
    (net (code "80") (name "Net-(LED35-CKO)") (class "Default")
      (node (ref "LED35") (pin "2") (pinfunction "CKO_2") (pintype "output"))
      (node (ref "LED36") (pin "5") (pinfunction "CKI_5") (pintype "input"))
    )
    (net (code "81") (name "Net-(LED35-DO)") (class "Default")
      (node (ref "LED35") (pin "1") (pinfunction "DO_1") (pintype "output"))
      (node (ref "LED36") (pin "6") (pinfunction "DI_6") (pintype "input"))
    )
    (net (code "82") (name "Net-(LED36-CKO)") (class "Default")
      (node (ref "LED36") (pin "2") (pinfunction "CKO_2") (pintype "output"))
      (node (ref "LED37") (pin "5") (pinfunction "CKI_5") (pintype "input"))
    )
    (net (code "83") (name "Net-(LED36-DO)") (class "Default")
      (node (ref "LED36") (pin "1") (pinfunction "DO_1") (pintype "output"))
      (node (ref "LED37") (pin "6") (pinfunction "DI_6") (pintype "input"))
    )
    (net (code "84") (name "Net-(LED37-CKO)") (class "Default")
      (node (ref "LED37") (pin "2") (pinfunction "CKO_2") (pintype "output"))
      (node (ref "LED38") (pin "5") (pinfunction "CKI_5") (pintype "input"))
    )
    (net (code "85") (name "Net-(LED37-DO)") (class "Default")
      (node (ref "LED37") (pin "1") (pinfunction "DO_1") (pintype "output"))
      (node (ref "LED38") (pin "6") (pinfunction "DI_6") (pintype "input"))
    )
    (net (code "86") (name "Net-(LED38-CKO)") (class "Default")
      (node (ref "LED38") (pin "2") (pinfunction "CKO_2") (pintype "output"))
      (node (ref "LED39") (pin "5") (pinfunction "CKI_5") (pintype "input"))
    )
    (net (code "87") (name "Net-(LED38-DO)") (class "Default")
      (node (ref "LED38") (pin "1") (pinfunction "DO_1") (pintype "output"))
      (node (ref "LED39") (pin "6") (pinfunction "DI_6") (pintype "input"))
    )
    (net (code "88") (name "Net-(LED39-CKO)") (class "Default")
      (node (ref "LED39") (pin "2") (pinfunction "CKO_2") (pintype "output"))
      (node (ref "LED40") (pin "5") (pinfunction "CKI_5") (pintype "input"))
    )
    (net (code "89") (name "Net-(LED39-DO)") (class "Default")
      (node (ref "LED39") (pin "1") (pinfunction "DO_1") (pintype "output"))
      (node (ref "LED40") (pin "6") (pinfunction "DI_6") (pintype "input"))
    )
    (net (code "90") (name "Net-(LED40-CKO)") (class "Default")
      (node (ref "LED40") (pin "2") (pinfunction "CKO_2") (pintype "output"))
      (node (ref "LED65") (pin "5") (pinfunction "CKI_5") (pintype "input"))
    )
    (net (code "91") (name "Net-(LED40-DO)") (class "Default")
      (node (ref "LED40") (pin "1") (pinfunction "DO_1") (pintype "output"))
      (node (ref "LED65") (pin "6") (pinfunction "DI_6") (pintype "input"))
    )
    (net (code "92") (name "Net-(LED41-CKI)") (class "Default")
      (node (ref "LED41") (pin "5") (pinfunction "CKI_5") (pintype "input"))
      (node (ref "LED68") (pin "2") (pinfunction "CKO_2") (pintype "output"))
    )
    (net (code "93") (name "Net-(LED41-CKO)") (class "Default")
      (node (ref "LED41") (pin "2") (pinfunction "CKO_2") (pintype "output"))
      (node (ref "LED42") (pin "5") (pinfunction "CKI_5") (pintype "input"))
    )
    (net (code "94") (name "Net-(LED41-DI)") (class "Default")
      (node (ref "LED41") (pin "6") (pinfunction "DI_6") (pintype "input"))
      (node (ref "LED68") (pin "1") (pinfunction "DO_1") (pintype "output"))
    )
    (net (code "95") (name "Net-(LED41-DO)") (class "Default")
      (node (ref "LED41") (pin "1") (pinfunction "DO_1") (pintype "output"))
      (node (ref "LED42") (pin "6") (pinfunction "DI_6") (pintype "input"))
    )
    (net (code "96") (name "Net-(LED42-CKO)") (class "Default")
      (node (ref "LED42") (pin "2") (pinfunction "CKO_2") (pintype "output"))
      (node (ref "LED43") (pin "5") (pinfunction "CKI_5") (pintype "input"))
    )
    (net (code "97") (name "Net-(LED42-DO)") (class "Default")
      (node (ref "LED42") (pin "1") (pinfunction "DO_1") (pintype "output"))
      (node (ref "LED43") (pin "6") (pinfunction "DI_6") (pintype "input"))
    )
    (net (code "98") (name "Net-(LED43-CKO)") (class "Default")
      (node (ref "LED43") (pin "2") (pinfunction "CKO_2") (pintype "output"))
      (node (ref "LED44") (pin "5") (pinfunction "CKI_5") (pintype "input"))
    )
    (net (code "99") (name "Net-(LED43-DO)") (class "Default")
      (node (ref "LED43") (pin "1") (pinfunction "DO_1") (pintype "output"))
      (node (ref "LED44") (pin "6") (pinfunction "DI_6") (pintype "input"))
    )
    (net (code "100") (name "Net-(LED44-CKO)") (class "Default")
      (node (ref "LED44") (pin "2") (pinfunction "CKO_2") (pintype "output"))
      (node (ref "LED45") (pin "5") (pinfunction "CKI_5") (pintype "input"))
    )
    (net (code "101") (name "Net-(LED44-DO)") (class "Default")
      (node (ref "LED44") (pin "1") (pinfunction "DO_1") (pintype "output"))
      (node (ref "LED45") (pin "6") (pinfunction "DI_6") (pintype "input"))
    )
    (net (code "102") (name "Net-(LED45-CKO)") (class "Default")
      (node (ref "LED45") (pin "2") (pinfunction "CKO_2") (pintype "output"))
      (node (ref "LED46") (pin "5") (pinfunction "CKI_5") (pintype "input"))
    )
    (net (code "103") (name "Net-(LED45-DO)") (class "Default")
      (node (ref "LED45") (pin "1") (pinfunction "DO_1") (pintype "output"))
      (node (ref "LED46") (pin "6") (pinfunction "DI_6") (pintype "input"))
    )
    (net (code "104") (name "Net-(LED46-CKO)") (class "Default")
      (node (ref "LED46") (pin "2") (pinfunction "CKO_2") (pintype "output"))
      (node (ref "LED47") (pin "5") (pinfunction "CKI_5") (pintype "input"))
    )
    (net (code "105") (name "Net-(LED46-DO)") (class "Default")
      (node (ref "LED46") (pin "1") (pinfunction "DO_1") (pintype "output"))
      (node (ref "LED47") (pin "6") (pinfunction "DI_6") (pintype "input"))
    )
    (net (code "106") (name "Net-(LED47-CKO)") (class "Default")
      (node (ref "LED47") (pin "2") (pinfunction "CKO_2") (pintype "output"))
      (node (ref "LED48") (pin "5") (pinfunction "CKI_5") (pintype "input"))
    )
    (net (code "107") (name "Net-(LED47-DO)") (class "Default")
      (node (ref "LED47") (pin "1") (pinfunction "DO_1") (pintype "output"))
      (node (ref "LED48") (pin "6") (pinfunction "DI_6") (pintype "input"))
    )
    (net (code "108") (name "Net-(LED48-CKO)") (class "Default")
      (node (ref "LED48") (pin "2") (pinfunction "CKO_2") (pintype "output"))
      (node (ref "LED69") (pin "5") (pinfunction "CKI_5") (pintype "input"))
    )
    (net (code "109") (name "Net-(LED48-DO)") (class "Default")
      (node (ref "LED48") (pin "1") (pinfunction "DO_1") (pintype "output"))
      (node (ref "LED69") (pin "6") (pinfunction "DI_6") (pintype "input"))
    )
    (net (code "110") (name "Net-(LED49-CKI)") (class "Default")
      (node (ref "LED49") (pin "5") (pinfunction "CKI_5") (pintype "input"))
      (node (ref "LED8") (pin "2") (pinfunction "CKO_2") (pintype "output"))
    )
    (net (code "111") (name "Net-(LED49-CKO)") (class "Default")
      (node (ref "LED49") (pin "2") (pinfunction "CKO_2") (pintype "output"))
      (node (ref "LED50") (pin "5") (pinfunction "CKI_5") (pintype "input"))
    )
    (net (code "112") (name "Net-(LED49-DI)") (class "Default")
      (node (ref "LED49") (pin "6") (pinfunction "DI_6") (pintype "input"))
      (node (ref "LED8") (pin "1") (pinfunction "DO_1") (pintype "output"))
    )
    (net (code "113") (name "Net-(LED49-DO)") (class "Default")
      (node (ref "LED49") (pin "1") (pinfunction "DO_1") (pintype "output"))
      (node (ref "LED50") (pin "6") (pinfunction "DI_6") (pintype "input"))
    )
    (net (code "114") (name "Net-(LED50-CKO)") (class "Default")
      (node (ref "LED50") (pin "2") (pinfunction "CKO_2") (pintype "output"))
      (node (ref "LED51") (pin "5") (pinfunction "CKI_5") (pintype "input"))
    )
    (net (code "115") (name "Net-(LED50-DO)") (class "Default")
      (node (ref "LED50") (pin "1") (pinfunction "DO_1") (pintype "output"))
      (node (ref "LED51") (pin "6") (pinfunction "DI_6") (pintype "input"))
    )
    (net (code "116") (name "Net-(LED51-CKO)") (class "Default")
      (node (ref "LED51") (pin "2") (pinfunction "CKO_2") (pintype "output"))
      (node (ref "LED52") (pin "5") (pinfunction "CKI_5") (pintype "input"))
    )
    (net (code "117") (name "Net-(LED51-DO)") (class "Default")
      (node (ref "LED51") (pin "1") (pinfunction "DO_1") (pintype "output"))
      (node (ref "LED52") (pin "6") (pinfunction "DI_6") (pintype "input"))
    )
    (net (code "118") (name "Net-(LED52-CKO)") (class "Default")
      (node (ref "LED52") (pin "2") (pinfunction "CKO_2") (pintype "output"))
      (node (ref "LED9") (pin "5") (pinfunction "CKI_5") (pintype "input"))
    )
    (net (code "119") (name "Net-(LED52-DO)") (class "Default")
      (node (ref "LED52") (pin "1") (pinfunction "DO_1") (pintype "output"))
      (node (ref "LED9") (pin "6") (pinfunction "DI_6") (pintype "input"))
    )
    (net (code "120") (name "Net-(LED53-CKO)") (class "Default")
      (node (ref "LED53") (pin "2") (pinfunction "CKO_2") (pintype "output"))
      (node (ref "LED54") (pin "5") (pinfunction "CKI_5") (pintype "input"))
    )
    (net (code "121") (name "Net-(LED53-DO)") (class "Default")
      (node (ref "LED53") (pin "1") (pinfunction "DO_1") (pintype "output"))
      (node (ref "LED54") (pin "6") (pinfunction "DI_6") (pintype "input"))
    )
    (net (code "122") (name "Net-(LED54-CKO)") (class "Default")
      (node (ref "LED54") (pin "2") (pinfunction "CKO_2") (pintype "output"))
      (node (ref "LED55") (pin "5") (pinfunction "CKI_5") (pintype "input"))
    )
    (net (code "123") (name "Net-(LED54-DO)") (class "Default")
      (node (ref "LED54") (pin "1") (pinfunction "DO_1") (pintype "output"))
      (node (ref "LED55") (pin "6") (pinfunction "DI_6") (pintype "input"))
    )
    (net (code "124") (name "Net-(LED55-CKO)") (class "Default")
      (node (ref "LED55") (pin "2") (pinfunction "CKO_2") (pintype "output"))
      (node (ref "LED56") (pin "5") (pinfunction "CKI_5") (pintype "input"))
    )
    (net (code "125") (name "Net-(LED55-DO)") (class "Default")
      (node (ref "LED55") (pin "1") (pinfunction "DO_1") (pintype "output"))
      (node (ref "LED56") (pin "6") (pinfunction "DI_6") (pintype "input"))
    )
    (net (code "126") (name "Net-(LED57-CKO)") (class "Default")
      (node (ref "LED57") (pin "2") (pinfunction "CKO_2") (pintype "output"))
      (node (ref "LED58") (pin "5") (pinfunction "CKI_5") (pintype "input"))
    )
    (net (code "127") (name "Net-(LED57-DO)") (class "Default")
      (node (ref "LED57") (pin "1") (pinfunction "DO_1") (pintype "output"))
      (node (ref "LED58") (pin "6") (pinfunction "DI_6") (pintype "input"))
    )
    (net (code "128") (name "Net-(LED58-CKO)") (class "Default")
      (node (ref "LED58") (pin "2") (pinfunction "CKO_2") (pintype "output"))
      (node (ref "LED59") (pin "5") (pinfunction "CKI_5") (pintype "input"))
    )
    (net (code "129") (name "Net-(LED58-DO)") (class "Default")
      (node (ref "LED58") (pin "1") (pinfunction "DO_1") (pintype "output"))
      (node (ref "LED59") (pin "6") (pinfunction "DI_6") (pintype "input"))
    )
    (net (code "130") (name "Net-(LED59-CKO)") (class "Default")
      (node (ref "LED59") (pin "2") (pinfunction "CKO_2") (pintype "output"))
      (node (ref "LED60") (pin "5") (pinfunction "CKI_5") (pintype "input"))
    )
    (net (code "131") (name "Net-(LED59-DO)") (class "Default")
      (node (ref "LED59") (pin "1") (pinfunction "DO_1") (pintype "output"))
      (node (ref "LED60") (pin "6") (pinfunction "DI_6") (pintype "input"))
    )
    (net (code "132") (name "Net-(LED61-CKO)") (class "Default")
      (node (ref "LED61") (pin "2") (pinfunction "CKO_2") (pintype "output"))
      (node (ref "LED62") (pin "5") (pinfunction "CKI_5") (pintype "input"))
    )
    (net (code "133") (name "Net-(LED61-DO)") (class "Default")
      (node (ref "LED61") (pin "1") (pinfunction "DO_1") (pintype "output"))
      (node (ref "LED62") (pin "6") (pinfunction "DI_6") (pintype "input"))
    )
    (net (code "134") (name "Net-(LED62-CKO)") (class "Default")
      (node (ref "LED62") (pin "2") (pinfunction "CKO_2") (pintype "output"))
      (node (ref "LED63") (pin "5") (pinfunction "CKI_5") (pintype "input"))
    )
    (net (code "135") (name "Net-(LED62-DO)") (class "Default")
      (node (ref "LED62") (pin "1") (pinfunction "DO_1") (pintype "output"))
      (node (ref "LED63") (pin "6") (pinfunction "DI_6") (pintype "input"))
    )
    (net (code "136") (name "Net-(LED63-CKO)") (class "Default")
      (node (ref "LED63") (pin "2") (pinfunction "CKO_2") (pintype "output"))
      (node (ref "LED64") (pin "5") (pinfunction "CKI_5") (pintype "input"))
    )
    (net (code "137") (name "Net-(LED63-DO)") (class "Default")
      (node (ref "LED63") (pin "1") (pinfunction "DO_1") (pintype "output"))
      (node (ref "LED64") (pin "6") (pinfunction "DI_6") (pintype "input"))
    )
    (net (code "138") (name "Net-(LED65-CKO)") (class "Default")
      (node (ref "LED65") (pin "2") (pinfunction "CKO_2") (pintype "output"))
      (node (ref "LED66") (pin "5") (pinfunction "CKI_5") (pintype "input"))
    )
    (net (code "139") (name "Net-(LED65-DO)") (class "Default")
      (node (ref "LED65") (pin "1") (pinfunction "DO_1") (pintype "output"))
      (node (ref "LED66") (pin "6") (pinfunction "DI_6") (pintype "input"))
    )
    (net (code "140") (name "Net-(LED66-CKO)") (class "Default")
      (node (ref "LED66") (pin "2") (pinfunction "CKO_2") (pintype "output"))
      (node (ref "LED67") (pin "5") (pinfunction "CKI_5") (pintype "input"))
    )
    (net (code "141") (name "Net-(LED66-DO)") (class "Default")
      (node (ref "LED66") (pin "1") (pinfunction "DO_1") (pintype "output"))
      (node (ref "LED67") (pin "6") (pinfunction "DI_6") (pintype "input"))
    )
    (net (code "142") (name "Net-(LED67-CKO)") (class "Default")
      (node (ref "LED67") (pin "2") (pinfunction "CKO_2") (pintype "output"))
      (node (ref "LED68") (pin "5") (pinfunction "CKI_5") (pintype "input"))
    )
    (net (code "143") (name "Net-(LED67-DO)") (class "Default")
      (node (ref "LED67") (pin "1") (pinfunction "DO_1") (pintype "output"))
      (node (ref "LED68") (pin "6") (pinfunction "DI_6") (pintype "input"))
    )
    (net (code "144") (name "Net-(LED69-CKO)") (class "Default")
      (node (ref "LED69") (pin "2") (pinfunction "CKO_2") (pintype "output"))
      (node (ref "LED70") (pin "5") (pinfunction "CKI_5") (pintype "input"))
    )
    (net (code "145") (name "Net-(LED69-DO)") (class "Default")
      (node (ref "LED69") (pin "1") (pinfunction "DO_1") (pintype "output"))
      (node (ref "LED70") (pin "6") (pinfunction "DI_6") (pintype "input"))
    )
    (net (code "146") (name "Net-(LED70-CKO)") (class "Default")
      (node (ref "LED70") (pin "2") (pinfunction "CKO_2") (pintype "output"))
      (node (ref "LED71") (pin "5") (pinfunction "CKI_5") (pintype "input"))
    )
    (net (code "147") (name "Net-(LED70-DO)") (class "Default")
      (node (ref "LED70") (pin "1") (pinfunction "DO_1") (pintype "output"))
      (node (ref "LED71") (pin "6") (pinfunction "DI_6") (pintype "input"))
    )
    (net (code "148") (name "Net-(LED71-CKO)") (class "Default")
      (node (ref "LED71") (pin "2") (pinfunction "CKO_2") (pintype "output"))
      (node (ref "LED72") (pin "5") (pinfunction "CKI_5") (pintype "input"))
    )
    (net (code "149") (name "Net-(LED71-DO)") (class "Default")
      (node (ref "LED71") (pin "1") (pinfunction "DO_1") (pintype "output"))
      (node (ref "LED72") (pin "6") (pinfunction "DI_6") (pintype "input"))
    )
    (net (code "150") (name "Net-(MS1-GPIO5)") (class "Default")
      (node (ref "MS1") (pin "19") (pinfunction "GPIO5_19") (pintype "bidirectional"))
      (node (ref "TP1") (pin "P$1") (pinfunction "P$1_P$1") (pintype "bidirectional"))
    )
    (net (code "151") (name "Net-(MS1-GPIO6)") (class "Default")
      (node (ref "MS1") (pin "20") (pinfunction "GPIO6_20") (pintype "bidirectional"))
      (node (ref "TP3") (pin "P$1") (pinfunction "P$1_P$1") (pintype "bidirectional"))
    )
    (net (code "152") (name "Net-(MS1-GPIO9)") (class "Default")
      (node (ref "MS1") (pin "21") (pinfunction "GPIO9_21") (pintype "bidirectional"))
      (node (ref "TP2") (pin "P$1") (pinfunction "P$1_P$1") (pintype "bidirectional"))
    )
    (net (code "153") (name "Net-(MS1-GPIO10)") (class "Default")
      (node (ref "MS1") (pin "22") (pinfunction "GPIO10_22") (pintype "bidirectional"))
      (node (ref "TP4") (pin "P$1") (pinfunction "P$1_P$1") (pintype "bidirectional"))
    )
    (net (code "154") (name "Net-(MS1-GPIO11)") (class "Default")
      (node (ref "MS1") (pin "23") (pinfunction "GPIO11_23") (pintype "bidirectional"))
      (node (ref "SJ2") (pin "1") (pinfunction "1_1") (pintype "passive"))
    )
    (net (code "155") (name "Net-(MS1-GPIO13)") (class "Default")
      (node (ref "MS1") (pin "25") (pinfunction "GPIO13_25") (pintype "bidirectional"))
      (node (ref "SJ1") (pin "1") (pinfunction "1_1") (pintype "passive"))
    )
    (net (code "156") (name "Net-(MS1-GPIOA0)") (class "Default")
      (node (ref "MS1") (pin "5") (pinfunction "GPIOA0_5") (pintype "bidirectional"))
      (node (ref "TP8") (pin "P$1") (pinfunction "P$1_P$1") (pintype "bidirectional"))
    )
    (net (code "157") (name "Net-(MS1-GPIOA1)") (class "Default")
      (node (ref "MS1") (pin "6") (pinfunction "GPIOA1_6") (pintype "bidirectional"))
      (node (ref "TP11") (pin "P$1") (pinfunction "P$1_P$1") (pintype "bidirectional"))
    )
    (net (code "158") (name "Net-(MS1-GPIOA2)") (class "Default")
      (node (ref "MS1") (pin "7") (pinfunction "GPIOA2_7") (pintype "bidirectional"))
      (node (ref "TP10") (pin "P$1") (pinfunction "P$1_P$1") (pintype "bidirectional"))
    )
    (net (code "159") (name "Net-(MS1-GPIOA4)") (class "Default")
      (node (ref "MS1") (pin "9") (pinfunction "GPIOA4_9") (pintype "bidirectional"))
      (node (ref "TP9") (pin "P$1") (pinfunction "P$1_P$1") (pintype "bidirectional"))
    )
    (net (code "160") (name "Net-(MS1-GPIOA5)") (class "Default")
      (node (ref "MS1") (pin "10") (pinfunction "GPIOA5_10") (pintype "bidirectional"))
      (node (ref "TP7") (pin "P$1") (pinfunction "P$1_P$1") (pintype "bidirectional"))
    )
    (net (code "161") (name "Net-(MS1-GPIOMOSI)") (class "Default")
      (node (ref "MS1") (pin "12") (pinfunction "GPIOMOSI_12") (pintype "bidirectional"))
      (node (ref "TP6") (pin "P$1") (pinfunction "P$1_P$1") (pintype "bidirectional"))
    )
    (net (code "162") (name "Net-(MS1-GPIOSCK)") (class "Default")
      (node (ref "MS1") (pin "11") (pinfunction "GPIOSCK_11") (pintype "bidirectional"))
      (node (ref "TP5") (pin "P$1") (pinfunction "P$1_P$1") (pintype "bidirectional"))
    )
    (net (code "163") (name "Net-(Q3-S)") (class "Default")
      (node (ref "D1") (pin "C") (pinfunction "C_C") (pintype "passive"))
      (node (ref "D2") (pin "C") (pinfunction "C_C") (pintype "passive"))
      (node (ref "Q3") (pin "2") (pinfunction "S_2") (pintype "passive"))
      (node (ref "R12") (pin "2") (pinfunction "2_2") (pintype "passive"))
    )
    (net (code "164") (name "VBAT") (class "Default")
      (node (ref "D2") (pin "A") (pinfunction "A_A") (pintype "passive"))
      (node (ref "MS1") (pin "28") (pinfunction "VBAT_28") (pintype "power_in"))
    )
    (net (code "165") (name "VBUS") (class "Default")
      (node (ref "D1") (pin "A") (pinfunction "A_A") (pintype "passive"))
      (node (ref "MS1") (pin "26") (pinfunction "USB_26") (pintype "power_in"))
    )
    (net (code "166") (name "VDD") (class "Default")
      (node (ref "C1") (pin "1") (pinfunction "1_1") (pintype "passive"))
      (node (ref "C2") (pin "1") (pinfunction "1_1") (pintype "passive"))
      (node (ref "C3") (pin "1") (pinfunction "1_1") (pintype "passive"))
      (node (ref "C4") (pin "1") (pinfunction "1_1") (pintype "passive"))
      (node (ref "C5") (pin "1") (pinfunction "1_1") (pintype "passive"))
      (node (ref "C6") (pin "1") (pinfunction "1_1") (pintype "passive"))
      (node (ref "C7") (pin "1") (pinfunction "1_1") (pintype "passive"))
      (node (ref "C8") (pin "1") (pinfunction "1_1") (pintype "passive"))
      (node (ref "LED1") (pin "3") (pinfunction "VDD_3") (pintype "power_in"))
      (node (ref "LED10") (pin "3") (pinfunction "VDD_3") (pintype "power_in"))
      (node (ref "LED11") (pin "3") (pinfunction "VDD_3") (pintype "power_in"))
      (node (ref "LED12") (pin "3") (pinfunction "VDD_3") (pintype "power_in"))
      (node (ref "LED13") (pin "3") (pinfunction "VDD_3") (pintype "power_in"))
      (node (ref "LED14") (pin "3") (pinfunction "VDD_3") (pintype "power_in"))
      (node (ref "LED15") (pin "3") (pinfunction "VDD_3") (pintype "power_in"))
      (node (ref "LED16") (pin "3") (pinfunction "VDD_3") (pintype "power_in"))
      (node (ref "LED17") (pin "3") (pinfunction "VDD_3") (pintype "power_in"))
      (node (ref "LED18") (pin "3") (pinfunction "VDD_3") (pintype "power_in"))
      (node (ref "LED19") (pin "3") (pinfunction "VDD_3") (pintype "power_in"))
      (node (ref "LED2") (pin "3") (pinfunction "VDD_3") (pintype "power_in"))
      (node (ref "LED20") (pin "3") (pinfunction "VDD_3") (pintype "power_in"))
      (node (ref "LED21") (pin "3") (pinfunction "VDD_3") (pintype "power_in"))
      (node (ref "LED22") (pin "3") (pinfunction "VDD_3") (pintype "power_in"))
      (node (ref "LED23") (pin "3") (pinfunction "VDD_3") (pintype "power_in"))
      (node (ref "LED24") (pin "3") (pinfunction "VDD_3") (pintype "power_in"))
      (node (ref "LED25") (pin "3") (pinfunction "VDD_3") (pintype "power_in"))
      (node (ref "LED26") (pin "3") (pinfunction "VDD_3") (pintype "power_in"))
      (node (ref "LED27") (pin "3") (pinfunction "VDD_3") (pintype "power_in"))
      (node (ref "LED28") (pin "3") (pinfunction "VDD_3") (pintype "power_in"))
      (node (ref "LED29") (pin "3") (pinfunction "VDD_3") (pintype "power_in"))
      (node (ref "LED3") (pin "3") (pinfunction "VDD_3") (pintype "power_in"))
      (node (ref "LED30") (pin "3") (pinfunction "VDD_3") (pintype "power_in"))
      (node (ref "LED31") (pin "3") (pinfunction "VDD_3") (pintype "power_in"))
      (node (ref "LED32") (pin "3") (pinfunction "VDD_3") (pintype "power_in"))
      (node (ref "LED33") (pin "3") (pinfunction "VDD_3") (pintype "power_in"))
      (node (ref "LED34") (pin "3") (pinfunction "VDD_3") (pintype "power_in"))
      (node (ref "LED35") (pin "3") (pinfunction "VDD_3") (pintype "power_in"))
      (node (ref "LED36") (pin "3") (pinfunction "VDD_3") (pintype "power_in"))
      (node (ref "LED37") (pin "3") (pinfunction "VDD_3") (pintype "power_in"))
      (node (ref "LED38") (pin "3") (pinfunction "VDD_3") (pintype "power_in"))
      (node (ref "LED39") (pin "3") (pinfunction "VDD_3") (pintype "power_in"))
      (node (ref "LED4") (pin "3") (pinfunction "VDD_3") (pintype "power_in"))
      (node (ref "LED40") (pin "3") (pinfunction "VDD_3") (pintype "power_in"))
      (node (ref "LED41") (pin "3") (pinfunction "VDD_3") (pintype "power_in"))
      (node (ref "LED42") (pin "3") (pinfunction "VDD_3") (pintype "power_in"))
      (node (ref "LED43") (pin "3") (pinfunction "VDD_3") (pintype "power_in"))
      (node (ref "LED44") (pin "3") (pinfunction "VDD_3") (pintype "power_in"))
      (node (ref "LED45") (pin "3") (pinfunction "VDD_3") (pintype "power_in"))
      (node (ref "LED46") (pin "3") (pinfunction "VDD_3") (pintype "power_in"))
      (node (ref "LED47") (pin "3") (pinfunction "VDD_3") (pintype "power_in"))
      (node (ref "LED48") (pin "3") (pinfunction "VDD_3") (pintype "power_in"))
      (node (ref "LED49") (pin "3") (pinfunction "VDD_3") (pintype "power_in"))
      (node (ref "LED5") (pin "3") (pinfunction "VDD_3") (pintype "power_in"))
      (node (ref "LED50") (pin "3") (pinfunction "VDD_3") (pintype "power_in"))
      (node (ref "LED51") (pin "3") (pinfunction "VDD_3") (pintype "power_in"))
      (node (ref "LED52") (pin "3") (pinfunction "VDD_3") (pintype "power_in"))
      (node (ref "LED53") (pin "3") (pinfunction "VDD_3") (pintype "power_in"))
      (node (ref "LED54") (pin "3") (pinfunction "VDD_3") (pintype "power_in"))
      (node (ref "LED55") (pin "3") (pinfunction "VDD_3") (pintype "power_in"))
      (node (ref "LED56") (pin "3") (pinfunction "VDD_3") (pintype "power_in"))
      (node (ref "LED57") (pin "3") (pinfunction "VDD_3") (pintype "power_in"))
      (node (ref "LED58") (pin "3") (pinfunction "VDD_3") (pintype "power_in"))
      (node (ref "LED59") (pin "3") (pinfunction "VDD_3") (pintype "power_in"))
      (node (ref "LED6") (pin "3") (pinfunction "VDD_3") (pintype "power_in"))
      (node (ref "LED60") (pin "3") (pinfunction "VDD_3") (pintype "power_in"))
      (node (ref "LED61") (pin "3") (pinfunction "VDD_3") (pintype "power_in"))
      (node (ref "LED62") (pin "3") (pinfunction "VDD_3") (pintype "power_in"))
      (node (ref "LED63") (pin "3") (pinfunction "VDD_3") (pintype "power_in"))
      (node (ref "LED64") (pin "3") (pinfunction "VDD_3") (pintype "power_in"))
      (node (ref "LED65") (pin "3") (pinfunction "VDD_3") (pintype "power_in"))
      (node (ref "LED66") (pin "3") (pinfunction "VDD_3") (pintype "power_in"))
      (node (ref "LED67") (pin "3") (pinfunction "VDD_3") (pintype "power_in"))
      (node (ref "LED68") (pin "3") (pinfunction "VDD_3") (pintype "power_in"))
      (node (ref "LED69") (pin "3") (pinfunction "VDD_3") (pintype "power_in"))
      (node (ref "LED7") (pin "3") (pinfunction "VDD_3") (pintype "power_in"))
      (node (ref "LED70") (pin "3") (pinfunction "VDD_3") (pintype "power_in"))
      (node (ref "LED71") (pin "3") (pinfunction "VDD_3") (pintype "power_in"))
      (node (ref "LED72") (pin "3") (pinfunction "VDD_3") (pintype "power_in"))
      (node (ref "LED8") (pin "3") (pinfunction "VDD_3") (pintype "power_in"))
      (node (ref "LED9") (pin "3") (pinfunction "VDD_3") (pintype "power_in"))
      (node (ref "Q3") (pin "3") (pinfunction "D_3") (pintype "passive"))
    )
    (net (code "167") (name "unconnected-(LED72-CKO-Pad2)") (class "Default")
      (node (ref "LED72") (pin "2") (pinfunction "CKO_2") (pintype "output"))
    )
    (net (code "168") (name "unconnected-(LED72-DO-Pad1)") (class "Default")
      (node (ref "LED72") (pin "1") (pinfunction "DO_1") (pintype "output"))
    )
    (net (code "169") (name "unconnected-(MS1-AREF-Pad3)") (class "Default")
      (node (ref "MS1") (pin "3") (pinfunction "AREF_3") (pintype "passive"))
    )
    (net (code "170") (name "unconnected-(MS1-GPIO12-Pad24)") (class "Default")
      (node (ref "MS1") (pin "24") (pinfunction "GPIO12_24") (pintype "bidirectional"))
    )
    (net (code "171") (name "unconnected-(MS1-GPIOA3-Pad8)") (class "Default")
      (node (ref "MS1") (pin "8") (pinfunction "GPIOA3_8") (pintype "bidirectional"))
    )
    (net (code "172") (name "unconnected-(MS1-GPIOMISO-Pad13)") (class "Default")
      (node (ref "MS1") (pin "13") (pinfunction "GPIOMISO_13") (pintype "bidirectional"))
    )
    (net (code "173") (name "unconnected-(MS1-GPIORX-Pad14)") (class "Default")
      (node (ref "MS1") (pin "14") (pinfunction "GPIORX_14") (pintype "bidirectional"))
    )
    (net (code "174") (name "unconnected-(MS1-GPIOSCL-Pad18)") (class "Default")
      (node (ref "MS1") (pin "18") (pinfunction "GPIOSCL_18") (pintype "bidirectional"))
    )
    (net (code "175") (name "unconnected-(MS1-GPIOSDA-Pad17)") (class "Default")
      (node (ref "MS1") (pin "17") (pinfunction "GPIOSDA_17") (pintype "bidirectional"))
    )
    (net (code "176") (name "unconnected-(MS1-GPIOTX-Pad15)") (class "Default")
      (node (ref "MS1") (pin "15") (pinfunction "GPIOTX_15") (pintype "bidirectional"))
    )
    (net (code "177") (name "unconnected-(MS1-NC-Pad16)") (class "Default")
      (node (ref "MS1") (pin "16") (pinfunction "NC_16") (pintype "passive"))
    )
  )
)
